# Current_Scaler.net
KiCad netlist of a schematic drawn in Altium Designer
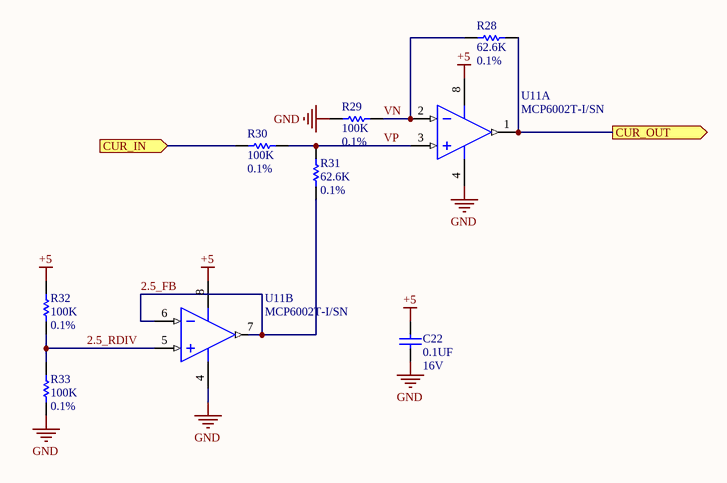
[diagram p0: Current Scaler.SchDoc]

(export (version "E")
  (design (tool "Eeschema 10.0.6"))
  (components
    (comp (ref "C22")
      (value "CAP 0603 0.1UF 16V 10% X7R")
      (footprint "0603_CAP")
      (description "Capacitor Surface Mount 0603 Footprint 0.1UF 16V 10% Tolerance Ceramic X7R")
      (fields
        (field (name "VAL") "0.1UF")
        (field (name "VOL") "16V")
        (field (name "MANUFACTURER") "Various")
        (field (name "VOLTAGE") "16V")
      )
      (libsource (lib "Passive Components") (part "cap"))
    )
    (comp (ref "R28")
      (value "RES 0603 62.6K 0.1%")
      (footprint "0603_RES")
      (description "Resistor Surface Mount, 51K Ohms, 0603 Footprint, 0.05% Tolerance 0.1W")
      (fields
        (field (name "VAL") "62.6K")
        (field (name "TOL") "0.1%")
        (field (name "MANUFACTURER") "Various")
        (field (name "TOLERANCE") "0.1%")
      )
      (libsource (lib "Passive Components") (part "res"))
    )
    (comp (ref "R29")
      (value "RES 0603 100K 0.1%")
      (footprint "0603_RES")
      (description "Resistor Surface Mount, 100K Ohms, 0603 Footprint, 0.1% Tolerance 0.1W")
      (fields
        (field (name "VAL") "100K")
        (field (name "TOL") "0.1%")
        (field (name "MANUFACTURER") "Various")
        (field (name "TOLERANCE") "0.1%")
      )
      (libsource (lib "Passive Components") (part "res"))
    )
    (comp (ref "R30")
      (value "RES 0603 100K 0.1%")
      (footprint "0603_RES")
      (description "Resistor Surface Mount, 100K Ohms, 0603 Footprint, 0.1% Tolerance 0.1W")
      (fields
        (field (name "VAL") "100K")
        (field (name "TOL") "0.1%")
        (field (name "MANUFACTURER") "Various")
        (field (name "TOLERANCE") "0.1%")
      )
      (libsource (lib "Passive Components") (part "res"))
    )
    (comp (ref "R31")
      (value "RES 0603 62.6K 0.1%")
      (footprint "0603_RES")
      (description "Resistor Surface Mount, 51K Ohms, 0603 Footprint, 0.05% Tolerance 0.1W")
      (fields
        (field (name "VAL") "62.6K")
        (field (name "TOL") "0.1%")
        (field (name "MANUFACTURER") "Various")
        (field (name "TOLERANCE") "0.1%")
      )
      (libsource (lib "Passive Components") (part "res"))
    )
    (comp (ref "R32")
      (value "RES 0603 100K 0.1%")
      (footprint "0603_RES")
      (description "Resistor Surface Mount, 100K Ohms, 0603 Footprint, 0.1% Tolerance 0.1W")
      (fields
        (field (name "VAL") "100K")
        (field (name "TOL") "0.1%")
        (field (name "MANUFACTURER") "Various")
        (field (name "TOLERANCE") "0.1%")
      )
      (libsource (lib "Passive Components") (part "res"))
    )
    (comp (ref "R33")
      (value "RES 0603 100K 0.1%")
      (footprint "0603_RES")
      (description "Resistor Surface Mount, 100K Ohms, 0603 Footprint, 0.1% Tolerance 0.1W")
      (fields
        (field (name "VAL") "100K")
        (field (name "TOL") "0.1%")
        (field (name "MANUFACTURER") "Various")
        (field (name "TOLERANCE") "0.1%")
      )
      (libsource (lib "Passive Components") (part "res"))
    )
    (comp (ref "U11")
      (value "MCP6002T-I/SN")
      (footprint "SOIC-SN8_L")
      (description "1 MHz, Low-Power Operational Amplifier, 8-Pin SOIC, Industrial Temperature, Tape and Reel")
      (libsource (lib "Altium Content Vault") (part "AMP-OPA-MCP6002-IL8"))
    )
  )
  (nets
    (net (code "1") (name "+5") (class "Default")
      (node (ref "C22") (pin "2") (pinfunction "2_2") (pintype "passive"))
      (node (ref "R32") (pin "2") (pinfunction "2_2") (pintype "passive"))
      (node (ref "U11") (pin "8") (pinfunction "VDD_8") (pintype "power_in"))
    )
    (net (code "2") (name "/2.5_FB") (class "Default")
      (node (ref "R31") (pin "1") (pinfunction "1_1") (pintype "passive"))
      (node (ref "U11") (pin "6") (pinfunction "VINB-_6") (pintype "input"))
      (node (ref "U11") (pin "7") (pinfunction "VOUTB_7") (pintype "output"))
    )
    (net (code "3") (name "/2.5_RDIV") (class "Default")
      (node (ref "R32") (pin "1") (pinfunction "1_1") (pintype "passive"))
      (node (ref "R33") (pin "2") (pinfunction "2_2") (pintype "passive"))
      (node (ref "U11") (pin "5") (pinfunction "VINB+_5") (pintype "input"))
    )
    (net (code "4") (name "/CUR_IN") (class "Default")
      (node (ref "R30") (pin "1") (pinfunction "1_1") (pintype "passive"))
    )
    (net (code "5") (name "/CUR_OUT") (class "Default")
      (node (ref "R28") (pin "1") (pinfunction "1_1") (pintype "passive"))
      (node (ref "U11") (pin "1") (pinfunction "VOUTA_1") (pintype "output"))
    )
    (net (code "6") (name "/VN") (class "Default")
      (node (ref "R28") (pin "2") (pinfunction "2_2") (pintype "passive"))
      (node (ref "R29") (pin "2") (pinfunction "2_2") (pintype "passive"))
      (node (ref "U11") (pin "2") (pinfunction "VINA-_2") (pintype "input"))
    )
    (net (code "7") (name "/VP") (class "Default")
      (node (ref "R30") (pin "2") (pinfunction "2_2") (pintype "passive"))
      (node (ref "R31") (pin "2") (pinfunction "2_2") (pintype "passive"))
      (node (ref "U11") (pin "3") (pinfunction "VINA+_3") (pintype "input"))
    )
    (net (code "8") (name "GND") (class "Default")
      (node (ref "C22") (pin "1") (pinfunction "1_1") (pintype "passive"))
      (node (ref "R29") (pin "1") (pinfunction "1_1") (pintype "passive"))
      (node (ref "R33") (pin "1") (pinfunction "1_1") (pintype "passive"))
      (node (ref "U11") (pin "4") (pinfunction "VSS_4") (pintype "power_in"))
    )
  )
)
